# ROV_SensorBoard.net
KiCad netlist of a schematic drawn in Altium Designer
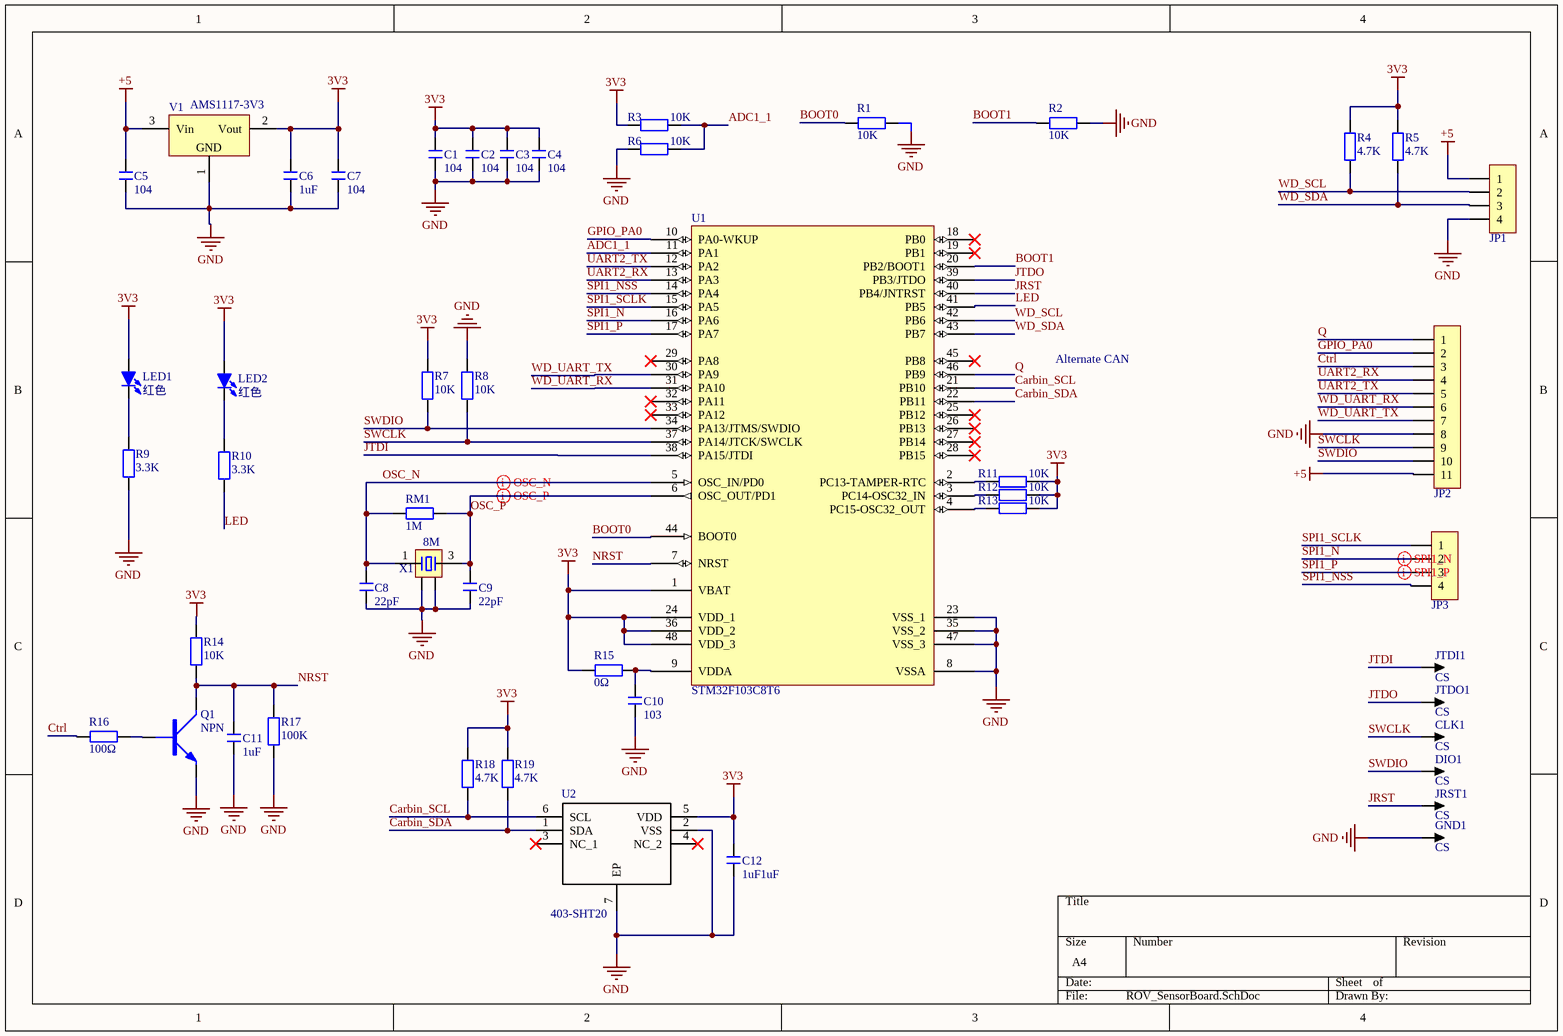
[diagram p0: ROV_SensorBoard.SchDoc]

(export (version "E")
  (design (tool "Eeschema 10.0.6"))
  (components
    (comp (ref "C1")
      (value "104")
      (footprint "C 0603_L")
      (description "无极性贴片电容")
      (fields (field (name "版权归属") "源创客"))
      (libsource (lib "3.1   - 电阻-电容-电感") (part "C"))
    )
    (comp (ref "C2")
      (value "104")
      (footprint "C 0603_L")
      (description "无极性贴片电容")
      (fields (field (name "版权归属") "源创客"))
      (libsource (lib "3.1   - 电阻-电容-电感") (part "C"))
    )
    (comp (ref "C3")
      (value "104")
      (footprint "C 0603_L")
      (description "无极性贴片电容")
      (fields (field (name "版权归属") "源创客"))
      (libsource (lib "3.1   - 电阻-电容-电感") (part "C"))
    )
    (comp (ref "C4")
      (value "104")
      (footprint "C 0603_L")
      (description "无极性贴片电容")
      (fields (field (name "版权归属") "源创客"))
      (libsource (lib "3.1   - 电阻-电容-电感") (part "C"))
    )
    (comp (ref "C5")
      (value "104")
      (footprint "C 0603_L")
      (description "无极性贴片电容")
      (fields (field (name "版权归属") "源创客"))
      (libsource (lib "3.1   - 电阻-电容-电感") (part "C"))
    )
    (comp (ref "C6")
      (value "1uF")
      (footprint "C 0603_L")
      (description "无极性贴片电容")
      (fields (field (name "版权归属") "源创客"))
      (libsource (lib "3.1   - 电阻-电容-电感") (part "C"))
    )
    (comp (ref "C7")
      (value "104")
      (footprint "C 0603_L")
      (description "无极性贴片电容")
      (fields (field (name "版权归属") "源创客"))
      (libsource (lib "3.1   - 电阻-电容-电感") (part "C"))
    )
    (comp (ref "C8")
      (value "22pF")
      (footprint "C 0603_L")
      (description "无极性贴片电容")
      (fields (field (name "版权归属") "源创客"))
      (libsource (lib "3.1   - 电阻-电容-电感") (part "C"))
    )
    (comp (ref "C9")
      (value "22pF")
      (footprint "C 0603_L")
      (description "无极性贴片电容")
      (fields (field (name "版权归属") "源创客"))
      (libsource (lib "3.1   - 电阻-电容-电感") (part "C"))
    )
    (comp (ref "C10")
      (value "103")
      (footprint "C 0603_L")
      (description "无极性贴片电容")
      (fields (field (name "版权归属") "源创客"))
      (libsource (lib "3.1   - 电阻-电容-电感") (part "C"))
    )
    (comp (ref "C11")
      (value "1uF")
      (footprint "C 0603_L")
      (description "无极性贴片电容")
      (fields (field (name "版权归属") "源创客"))
      (libsource (lib "3.1   - 电阻-电容-电感") (part "C"))
    )
    (comp (ref "C12")
      (value "1uF1uF")
      (footprint "C 0603_L")
      (description "无极性贴片电容")
      (fields (field (name "版权归属") "源创客"))
      (libsource (lib "3.1   - 电阻-电容-电感") (part "C"))
    )
    (comp (ref "CLK1")
      (value "CS")
      (footprint "R100")
      (description "探针焊盘")
      (fields (field (name "版权归属") "源创客"))
      (libsource (lib "15.1 - 未分类器件") (part "CS"))
    )
    (comp (ref "DIO1")
      (value "CS")
      (footprint "R100")
      (description "探针焊盘")
      (fields (field (name "版权归属") "源创客"))
      (libsource (lib "15.1 - 未分类器件") (part "CS"))
    )
    (comp (ref "GND1")
      (value "CS")
      (footprint "R100")
      (description "探针焊盘")
      (fields (field (name "版权归属") "源创客"))
      (libsource (lib "15.1 - 未分类器件") (part "CS"))
    )
    (comp (ref "JP1")
      (value "HDR-1X4")
      (footprint "MX 1.25-LS-4P")
      (description "4P接插件")
      (fields (field (name "版权归属") "源创客"))
      (libsource (lib "4.2   - 接插件-脚距1.25") (part "Header 4"))
    )
    (comp (ref "JP2")
      (value "HDR-1X11")
      (footprint "HDR2.54-LI-11P")
      (description "11P接插件")
      (fields (field (name "版权归属") "源创客"))
      (libsource (lib "4.5   - 接插件-脚距2.54") (part "Header 11"))
    )
    (comp (ref "JP3")
      (value "HDR-1X4")
      (footprint "HDR2.54-LI-4P")
      (description "4P接插件")
      (fields (field (name "版权归属") "源创客"))
      (libsource (lib "4.5   - 接插件-脚距2.54") (part "Header 4"))
    )
    (comp (ref "JRST1")
      (value "CS")
      (footprint "R100")
      (description "探针焊盘")
      (fields (field (name "版权归属") "源创客"))
      (libsource (lib "15.1 - 未分类器件") (part "CS"))
    )
    (comp (ref "JTDI1")
      (value "CS")
      (footprint "R100")
      (description "探针焊盘")
      (fields (field (name "版权归属") "源创客"))
      (libsource (lib "15.1 - 未分类器件") (part "CS"))
    )
    (comp (ref "JTDO1")
      (value "CS")
      (footprint "R100")
      (description "探针焊盘")
      (fields (field (name "版权归属") "源创客"))
      (libsource (lib "15.1 - 未分类器件") (part "CS"))
    )
    (comp (ref "LED1")
      (value "红色")
      (footprint "LED 0603W")
      (description "贴片LED")
      (fields (field (name "版权归属") "源创客"))
      (libsource (lib "9.1   - LED") (part "LED-SMD"))
    )
    (comp (ref "LED2")
      (value "红色")
      (footprint "LED 0603W")
      (description "贴片LED")
      (fields (field (name "版权归属") "源创客"))
      (libsource (lib "9.1   - LED") (part "LED-SMD"))
    )
    (comp (ref "Q1")
      (value "NPN")
      (footprint "SOT-23")
      (description "NPN三极管")
      (libsource (lib "三极管") (part "NPN"))
    )
    (comp (ref "R1")
      (value "10K")
      (footprint "R 0603_L")
      (description "贴片电阻")
      (fields (field (name "版权归属") "源创客"))
      (libsource (lib "3.1   - 电阻-电容-电感") (part "R"))
    )
    (comp (ref "R2")
      (value "10K")
      (footprint "R 0603_L")
      (description "贴片电阻")
      (fields (field (name "版权归属") "源创客"))
      (libsource (lib "3.1   - 电阻-电容-电感") (part "R"))
    )
    (comp (ref "R3")
      (value "10K")
      (footprint "R 0603_L")
      (description "贴片电阻")
      (fields (field (name "版权归属") "源创客"))
      (libsource (lib "3.1   - 电阻-电容-电感") (part "R"))
    )
    (comp (ref "R4")
      (value "4.7K")
      (footprint "R 0603_L")
      (description "贴片电阻")
      (fields (field (name "版权归属") "源创客"))
      (libsource (lib "3.1   - 电阻-电容-电感") (part "R"))
    )
    (comp (ref "R5")
      (value "4.7K")
      (footprint "R 0603_L")
      (description "贴片电阻")
      (fields (field (name "版权归属") "源创客"))
      (libsource (lib "3.1   - 电阻-电容-电感") (part "R"))
    )
    (comp (ref "R6")
      (value "10K")
      (footprint "R 0603_L")
      (description "贴片电阻")
      (fields (field (name "版权归属") "源创客"))
      (libsource (lib "3.1   - 电阻-电容-电感") (part "R"))
    )
    (comp (ref "R7")
      (value "10K")
      (footprint "R 0603_L")
      (description "贴片电阻")
      (fields (field (name "版权归属") "源创客"))
      (libsource (lib "3.1   - 电阻-电容-电感") (part "R"))
    )
    (comp (ref "R8")
      (value "10K")
      (footprint "R 0603_L")
      (description "贴片电阻")
      (fields (field (name "版权归属") "源创客"))
      (libsource (lib "3.1   - 电阻-电容-电感") (part "R"))
    )
    (comp (ref "R9")
      (value "3.3K")
      (footprint "R 0603_L")
      (description "贴片电阻")
      (fields (field (name "版权归属") "源创客"))
      (libsource (lib "3.1   - 电阻-电容-电感") (part "R"))
    )
    (comp (ref "R10")
      (value "3.3K")
      (footprint "R 0603_L")
      (description "贴片电阻")
      (fields (field (name "版权归属") "源创客"))
      (libsource (lib "3.1   - 电阻-电容-电感") (part "R"))
    )
    (comp (ref "R11")
      (value "10K")
      (footprint "R 0603_L")
      (description "贴片电阻")
      (fields (field (name "版权归属") "源创客"))
      (libsource (lib "3.1   - 电阻-电容-电感") (part "R"))
    )
    (comp (ref "R12")
      (value "10K")
      (footprint "R 0603_L")
      (description "贴片电阻")
      (fields (field (name "版权归属") "源创客"))
      (libsource (lib "3.1   - 电阻-电容-电感") (part "R"))
    )
    (comp (ref "R13")
      (value "10K")
      (footprint "R 0603_L")
      (description "贴片电阻")
      (fields (field (name "版权归属") "源创客"))
      (libsource (lib "3.1   - 电阻-电容-电感") (part "R"))
    )
    (comp (ref "R14")
      (value "10K")
      (footprint "R 0603_L")
      (description "贴片电阻")
      (fields (field (name "版权归属") "源创客"))
      (libsource (lib "3.1   - 电阻-电容-电感") (part "R"))
    )
    (comp (ref "R15")
      (value "0Ω")
      (footprint "R 0603_L")
      (description "贴片电阻")
      (fields (field (name "版权归属") "源创客"))
      (libsource (lib "3.1   - 电阻-电容-电感") (part "R"))
    )
    (comp (ref "R16")
      (value "100Ω")
      (footprint "R 0603_L")
      (description "贴片电阻")
      (fields (field (name "版权归属") "源创客"))
      (libsource (lib "3.1   - 电阻-电容-电感") (part "R"))
    )
    (comp (ref "R17")
      (value "100K")
      (footprint "R 0603_L")
      (description "贴片电阻")
      (fields (field (name "版权归属") "源创客"))
      (libsource (lib "3.1   - 电阻-电容-电感") (part "R"))
    )
    (comp (ref "R18")
      (value "4.7K")
      (footprint "R 0603_L")
      (description "贴片电阻")
      (fields (field (name "版权归属") "源创客"))
      (libsource (lib "3.1   - 电阻-电容-电感") (part "R"))
    )
    (comp (ref "R19")
      (value "4.7K")
      (footprint "R 0603_L")
      (description "贴片电阻")
      (fields (field (name "版权归属") "源创客"))
      (libsource (lib "3.1   - 电阻-电容-电感") (part "R"))
    )
    (comp (ref "RM1")
      (value "1M")
      (footprint "R 0603_L")
      (description "贴片电阻")
      (fields (field (name "版权归属") "源创客"))
      (libsource (lib "3.1   - 电阻-电容-电感") (part "R"))
    )
    (comp (ref "U1")
      (value "STM32F103C8T6")
      (footprint "LQFP48 7X7")
      (libsource (lib "STM32系列") (part "STM32F103C8T6"))
    )
    (comp (ref "U2")
      (value "SHT20")
      (footprint "SON100P300X300X110-7N")
      (description "温湿度传感器")
      (fields (field (name "RS PART NUMBER") "1237351P") (field (name "MOUSER PART NUMBER") "403-SHT20"))
      (libsource (lib "MySchLib") (part "SHT20"))
    )
    (comp (ref "V1")
      (value "AMS1117-3V3")
      (footprint "SOT89_N")
      (description "三端稳压芯片")
      (fields (field (name "版权归属") "源创客"))
      (libsource (lib "1.3   - 电源类芯片") (part "AMS1117"))
    )
    (comp (ref "X1")
      (value "8M")
      (footprint "OSC 5032-4P")
      (description "4脚无源晶振")
      (fields (field (name "版权归属") "源创客"))
      (libsource (lib "10.1 - 保险丝-晶振") (part "XTAL-4P"))
    )
  )
  (nets
    (net (code "1") (name "+5") (class "Default")
      (node (ref "C5") (pin "2") (pinfunction "2_2") (pintype "passive"))
      (node (ref "JP1") (pin "1") (pinfunction "1_1") (pintype "passive"))
      (node (ref "JP2") (pin "11") (pinfunction "11_11") (pintype "passive"))
      (node (ref "V1") (pin "3") (pinfunction "Vin_3") (pintype "passive"))
    )
    (net (code "2") (name "/ADC1_1") (class "Default")
      (node (ref "R3") (pin "1") (pinfunction "1_1") (pintype "passive"))
      (node (ref "R6") (pin "1") (pinfunction "1_1") (pintype "passive"))
      (node (ref "U1") (pin "11") (pinfunction "PA1_11") (pintype "bidirectional"))
    )
    (net (code "3") (name "/BOOT0") (class "Default")
      (node (ref "R1") (pin "2") (pinfunction "2_2") (pintype "passive"))
      (node (ref "U1") (pin "44") (pinfunction "BOOT0_44") (pintype "input"))
    )
    (net (code "4") (name "/BOOT1") (class "Default")
      (node (ref "R2") (pin "2") (pinfunction "2_2") (pintype "passive"))
      (node (ref "U1") (pin "20") (pinfunction "PB2/BOOT1_20") (pintype "bidirectional"))
    )
    (net (code "5") (name "/Carbin_SCL") (class "Default")
      (node (ref "R18") (pin "1") (pinfunction "1_1") (pintype "passive"))
      (node (ref "U1") (pin "21") (pinfunction "PB10_21") (pintype "bidirectional"))
      (node (ref "U2") (pin "6") (pinfunction "SCL_6") (pintype "passive"))
    )
    (net (code "6") (name "/Carbin_SDA") (class "Default")
      (node (ref "R19") (pin "1") (pinfunction "1_1") (pintype "passive"))
      (node (ref "U1") (pin "22") (pinfunction "PB11_22") (pintype "bidirectional"))
      (node (ref "U2") (pin "1") (pinfunction "SDA_1") (pintype "passive"))
    )
    (net (code "7") (name "/Ctrl") (class "Default")
      (node (ref "JP2") (pin "3") (pinfunction "3_3") (pintype "passive"))
      (node (ref "R16") (pin "2") (pinfunction "2_2") (pintype "passive"))
    )
    (net (code "8") (name "/GPIO_PA0") (class "Default")
      (node (ref "JP2") (pin "2") (pinfunction "2_2") (pintype "passive"))
      (node (ref "U1") (pin "10") (pinfunction "PA0-WKUP_10") (pintype "bidirectional"))
    )
    (net (code "9") (name "/JRST") (class "Default")
      (node (ref "JRST1") (pin "1") (pinfunction "1_1") (pintype "passive"))
      (node (ref "U1") (pin "40") (pinfunction "PB4/JNTRST_40") (pintype "bidirectional"))
    )
    (net (code "10") (name "/JTDI") (class "Default")
      (node (ref "JTDI1") (pin "1") (pinfunction "1_1") (pintype "passive"))
      (node (ref "U1") (pin "38") (pinfunction "PA15/JTDI_38") (pintype "bidirectional"))
    )
    (net (code "11") (name "/JTDO") (class "Default")
      (node (ref "JTDO1") (pin "1") (pinfunction "1_1") (pintype "passive"))
      (node (ref "U1") (pin "39") (pinfunction "PB3/JTDO_39") (pintype "bidirectional"))
    )
    (net (code "12") (name "/LED") (class "Default")
      (node (ref "R10") (pin "1") (pinfunction "1_1") (pintype "passive"))
      (node (ref "U1") (pin "41") (pinfunction "PB5_41") (pintype "bidirectional"))
    )
    (net (code "13") (name "/NRST") (class "Default")
      (node (ref "C11") (pin "2") (pinfunction "2_2") (pintype "passive"))
      (node (ref "Q1") (pin "C") (pinfunction "C_C") (pintype "passive"))
      (node (ref "R14") (pin "2") (pinfunction "2_2") (pintype "passive"))
      (node (ref "R17") (pin "1") (pinfunction "1_1") (pintype "passive"))
      (node (ref "U1") (pin "7") (pinfunction "NRST_7") (pintype "bidirectional"))
    )
    (net (code "14") (name "/OSC_N") (class "Default")
      (node (ref "C8") (pin "2") (pinfunction "2_2") (pintype "passive"))
      (node (ref "RM1") (pin "2") (pinfunction "2_2") (pintype "passive"))
      (node (ref "U1") (pin "5") (pinfunction "OSC_IN/PD0_5") (pintype "input"))
      (node (ref "X1") (pin "1") (pinfunction "1_1") (pintype "passive"))
    )
    (net (code "15") (name "/OSC_P") (class "Default")
      (node (ref "C9") (pin "2") (pinfunction "2_2") (pintype "passive"))
      (node (ref "RM1") (pin "1") (pinfunction "1_1") (pintype "passive"))
      (node (ref "U1") (pin "6") (pinfunction "OSC_OUT/PD1_6") (pintype "output"))
      (node (ref "X1") (pin "3") (pinfunction "3_3") (pintype "passive"))
    )
    (net (code "16") (name "/Q") (class "Default")
      (node (ref "JP2") (pin "1") (pinfunction "1_1") (pintype "passive"))
      (node (ref "U1") (pin "46") (pinfunction "PB9_46") (pintype "bidirectional"))
    )
    (net (code "17") (name "/SPI1_N") (class "Default")
      (node (ref "JP3") (pin "2") (pinfunction "2_2") (pintype "passive"))
      (node (ref "U1") (pin "16") (pinfunction "PA6_16") (pintype "bidirectional"))
    )
    (net (code "18") (name "/SPI1_NSS") (class "Default")
      (node (ref "JP3") (pin "4") (pinfunction "4_4") (pintype "passive"))
      (node (ref "U1") (pin "14") (pinfunction "PA4_14") (pintype "bidirectional"))
    )
    (net (code "19") (name "/SPI1_P") (class "Default")
      (node (ref "JP3") (pin "3") (pinfunction "3_3") (pintype "passive"))
      (node (ref "U1") (pin "17") (pinfunction "PA7_17") (pintype "bidirectional"))
    )
    (net (code "20") (name "/SPI1_SCLK") (class "Default")
      (node (ref "JP3") (pin "1") (pinfunction "1_1") (pintype "passive"))
      (node (ref "U1") (pin "15") (pinfunction "PA5_15") (pintype "bidirectional"))
    )
    (net (code "21") (name "/SWCLK") (class "Default")
      (node (ref "CLK1") (pin "1") (pinfunction "1_1") (pintype "passive"))
      (node (ref "JP2") (pin "9") (pinfunction "9_9") (pintype "passive"))
      (node (ref "R8") (pin "2") (pinfunction "2_2") (pintype "passive"))
      (node (ref "U1") (pin "37") (pinfunction "PA14/JTCK/SWCLK_37") (pintype "bidirectional"))
    )
    (net (code "22") (name "/SWDIO") (class "Default")
      (node (ref "DIO1") (pin "1") (pinfunction "1_1") (pintype "passive"))
      (node (ref "JP2") (pin "10") (pinfunction "10_10") (pintype "passive"))
      (node (ref "R7") (pin "2") (pinfunction "2_2") (pintype "passive"))
      (node (ref "U1") (pin "34") (pinfunction "PA13/JTMS/SWDIO_34") (pintype "bidirectional"))
    )
    (net (code "23") (name "/UART2_RX") (class "Default")
      (node (ref "JP2") (pin "4") (pinfunction "4_4") (pintype "passive"))
      (node (ref "U1") (pin "13") (pinfunction "PA3_13") (pintype "bidirectional"))
    )
    (net (code "24") (name "/UART2_TX") (class "Default")
      (node (ref "JP2") (pin "5") (pinfunction "5_5") (pintype "passive"))
      (node (ref "U1") (pin "12") (pinfunction "PA2_12") (pintype "bidirectional"))
    )
    (net (code "25") (name "/WD_SCL") (class "Default")
      (node (ref "JP1") (pin "2") (pinfunction "2_2") (pintype "passive"))
      (node (ref "R4") (pin "1") (pinfunction "1_1") (pintype "passive"))
      (node (ref "U1") (pin "42") (pinfunction "PB6_42") (pintype "bidirectional"))
    )
    (net (code "26") (name "/WD_SDA") (class "Default")
      (node (ref "JP1") (pin "3") (pinfunction "3_3") (pintype "passive"))
      (node (ref "R5") (pin "1") (pinfunction "1_1") (pintype "passive"))
      (node (ref "U1") (pin "43") (pinfunction "PB7_43") (pintype "bidirectional"))
    )
    (net (code "27") (name "/WD_UART_RX") (class "Default")
      (node (ref "JP2") (pin "6") (pinfunction "6_6") (pintype "passive"))
      (node (ref "U1") (pin "31") (pinfunction "PA10_31") (pintype "bidirectional"))
    )
    (net (code "28") (name "/WD_UART_TX") (class "Default")
      (node (ref "JP2") (pin "7") (pinfunction "7_7") (pintype "passive"))
      (node (ref "U1") (pin "30") (pinfunction "PA9_30") (pintype "bidirectional"))
    )
    (net (code "29") (name "3V3") (class "Default")
      (node (ref "C1") (pin "2") (pinfunction "2_2") (pintype "passive"))
      (node (ref "C12") (pin "2") (pinfunction "2_2") (pintype "passive"))
      (node (ref "C2") (pin "2") (pinfunction "2_2") (pintype "passive"))
      (node (ref "C3") (pin "2") (pinfunction "2_2") (pintype "passive"))
      (node (ref "C4") (pin "2") (pinfunction "2_2") (pintype "passive"))
      (node (ref "C6") (pin "2") (pinfunction "2_2") (pintype "passive"))
      (node (ref "C7") (pin "2") (pinfunction "2_2") (pintype "passive"))
      (node (ref "LED1") (pin "1") (pinfunction "A_1") (pintype "passive"))
      (node (ref "LED2") (pin "1") (pinfunction "A_1") (pintype "passive"))
      (node (ref "R11") (pin "1") (pinfunction "1_1") (pintype "passive"))
      (node (ref "R12") (pin "1") (pinfunction "1_1") (pintype "passive"))
      (node (ref "R13") (pin "1") (pinfunction "1_1") (pintype "passive"))
      (node (ref "R14") (pin "1") (pinfunction "1_1") (pintype "passive"))
      (node (ref "R15") (pin "2") (pinfunction "2_2") (pintype "passive"))
      (node (ref "R18") (pin "2") (pinfunction "2_2") (pintype "passive"))
      (node (ref "R19") (pin "2") (pinfunction "2_2") (pintype "passive"))
      (node (ref "R3") (pin "2") (pinfunction "2_2") (pintype "passive"))
      (node (ref "R4") (pin "2") (pinfunction "2_2") (pintype "passive"))
      (node (ref "R5") (pin "2") (pinfunction "2_2") (pintype "passive"))
      (node (ref "R7") (pin "1") (pinfunction "1_1") (pintype "passive"))
      (node (ref "U1") (pin "1") (pinfunction "VBAT_1") (pintype "power_in"))
      (node (ref "U1") (pin "24") (pinfunction "VDD_1_24") (pintype "power_in"))
      (node (ref "U1") (pin "36") (pinfunction "VDD_2_36") (pintype "power_in"))
      (node (ref "U1") (pin "48") (pinfunction "VDD_3_48") (pintype "power_in"))
      (node (ref "U2") (pin "5") (pinfunction "VDD_5") (pintype "passive"))
      (node (ref "V1") (pin "2") (pinfunction "Vout_2") (pintype "passive"))
    )
    (net (code "30") (name "GND") (class "Default")
      (node (ref "C1") (pin "1") (pinfunction "1_1") (pintype "passive"))
      (node (ref "C10") (pin "1") (pinfunction "1_1") (pintype "passive"))
      (node (ref "C11") (pin "1") (pinfunction "1_1") (pintype "passive"))
      (node (ref "C12") (pin "1") (pinfunction "1_1") (pintype "passive"))
      (node (ref "C2") (pin "1") (pinfunction "1_1") (pintype "passive"))
      (node (ref "C3") (pin "1") (pinfunction "1_1") (pintype "passive"))
      (node (ref "C4") (pin "1") (pinfunction "1_1") (pintype "passive"))
      (node (ref "C5") (pin "1") (pinfunction "1_1") (pintype "passive"))
      (node (ref "C6") (pin "1") (pinfunction "1_1") (pintype "passive"))
      (node (ref "C7") (pin "1") (pinfunction "1_1") (pintype "passive"))
      (node (ref "C8") (pin "1") (pinfunction "1_1") (pintype "passive"))
      (node (ref "C9") (pin "1") (pinfunction "1_1") (pintype "passive"))
      (node (ref "GND1") (pin "1") (pinfunction "1_1") (pintype "passive"))
      (node (ref "JP1") (pin "4") (pinfunction "4_4") (pintype "passive"))
      (node (ref "JP2") (pin "8") (pinfunction "8_8") (pintype "passive"))
      (node (ref "Q1") (pin "E") (pinfunction "E_E") (pintype "passive"))
      (node (ref "R1") (pin "1") (pinfunction "1_1") (pintype "passive"))
      (node (ref "R17") (pin "2") (pinfunction "2_2") (pintype "passive"))
      (node (ref "R2") (pin "1") (pinfunction "1_1") (pintype "passive"))
      (node (ref "R6") (pin "2") (pinfunction "2_2") (pintype "passive"))
      (node (ref "R8") (pin "1") (pinfunction "1_1") (pintype "passive"))
      (node (ref "R9") (pin "1") (pinfunction "1_1") (pintype "passive"))
      (node (ref "U1") (pin "23") (pinfunction "VSS_1_23") (pintype "power_in"))
      (node (ref "U1") (pin "35") (pinfunction "VSS_2_35") (pintype "power_in"))
      (node (ref "U1") (pin "47") (pinfunction "VSS_3_47") (pintype "power_in"))
      (node (ref "U1") (pin "8") (pinfunction "VSSA_8") (pintype "power_in"))
      (node (ref "U2") (pin "2") (pinfunction "VSS_2") (pintype "passive"))
      (node (ref "U2") (pin "7") (pinfunction "EP_7") (pintype "passive"))
      (node (ref "V1") (pin "1") (pinfunction "GND_1") (pintype "passive"))
      (node (ref "X1") (pin "2") (pinfunction "2_2") (pintype "passive"))
      (node (ref "X1") (pin "4") (pinfunction "4_4") (pintype "passive"))
    )
    (net (code "31") (name "Net-(LED1-K)") (class "Default")
      (node (ref "LED1") (pin "2") (pinfunction "K_2") (pintype "passive"))
      (node (ref "R9") (pin "2") (pinfunction "2_2") (pintype "passive"))
    )
    (net (code "32") (name "Net-(LED2-K)") (class "Default")
      (node (ref "LED2") (pin "2") (pinfunction "K_2") (pintype "passive"))
      (node (ref "R10") (pin "2") (pinfunction "2_2") (pintype "passive"))
    )
    (net (code "33") (name "Net-(Q1-PadB)") (class "Default")
      (node (ref "Q1") (pin "B") (pinfunction "B_B") (pintype "passive"))
      (node (ref "R16") (pin "1") (pinfunction "1_1") (pintype "passive"))
    )
    (net (code "34") (name "Net-(U1-PC13-TAMPER-RTC)") (class "Default")
      (node (ref "R11") (pin "2") (pinfunction "2_2") (pintype "passive"))
      (node (ref "U1") (pin "2") (pinfunction "PC13-TAMPER-RTC_2") (pintype "bidirectional"))
    )
    (net (code "35") (name "Net-(U1-PC14-OSC32_IN)") (class "Default")
      (node (ref "R12") (pin "2") (pinfunction "2_2") (pintype "passive"))
      (node (ref "U1") (pin "3") (pinfunction "PC14-OSC32_IN_3") (pintype "bidirectional"))
    )
    (net (code "36") (name "Net-(U1-PC15-OSC32_OUT)") (class "Default")
      (node (ref "R13") (pin "2") (pinfunction "2_2") (pintype "passive"))
      (node (ref "U1") (pin "4") (pinfunction "PC15-OSC32_OUT_4") (pintype "bidirectional"))
    )
    (net (code "37") (name "Net-(U1-VDDA)") (class "Default")
      (node (ref "C10") (pin "2") (pinfunction "2_2") (pintype "passive"))
      (node (ref "R15") (pin "1") (pinfunction "1_1") (pintype "passive"))
      (node (ref "U1") (pin "9") (pinfunction "VDDA_9") (pintype "power_in"))
    )
    (net (code "38") (name "unconnected-(U1-PA8-Pad29)") (class "Default")
      (node (ref "U1") (pin "29") (pinfunction "PA8_29") (pintype "bidirectional+no_connect"))
    )
    (net (code "39") (name "unconnected-(U1-PA11-Pad32)") (class "Default")
      (node (ref "U1") (pin "32") (pinfunction "PA11_32") (pintype "bidirectional+no_connect"))
    )
    (net (code "40") (name "unconnected-(U1-PA12-Pad33)") (class "Default")
      (node (ref "U1") (pin "33") (pinfunction "PA12_33") (pintype "bidirectional+no_connect"))
    )
    (net (code "41") (name "unconnected-(U1-PB0-Pad18)") (class "Default")
      (node (ref "U1") (pin "18") (pinfunction "PB0_18") (pintype "bidirectional+no_connect"))
    )
    (net (code "42") (name "unconnected-(U1-PB1-Pad19)") (class "Default")
      (node (ref "U1") (pin "19") (pinfunction "PB1_19") (pintype "bidirectional+no_connect"))
    )
    (net (code "43") (name "unconnected-(U1-PB8-Pad45)") (class "Default")
      (node (ref "U1") (pin "45") (pinfunction "PB8_45") (pintype "bidirectional+no_connect"))
    )
    (net (code "44") (name "unconnected-(U1-PB12-Pad25)") (class "Default")
      (node (ref "U1") (pin "25") (pinfunction "PB12_25") (pintype "bidirectional+no_connect"))
    )
    (net (code "45") (name "unconnected-(U1-PB13-Pad26)") (class "Default")
      (node (ref "U1") (pin "26") (pinfunction "PB13_26") (pintype "bidirectional+no_connect"))
    )
    (net (code "46") (name "unconnected-(U1-PB14-Pad27)") (class "Default")
      (node (ref "U1") (pin "27") (pinfunction "PB14_27") (pintype "bidirectional+no_connect"))
    )
    (net (code "47") (name "unconnected-(U1-PB15-Pad28)") (class "Default")
      (node (ref "U1") (pin "28") (pinfunction "PB15_28") (pintype "bidirectional+no_connect"))
    )
    (net (code "48") (name "unconnected-(U2-NC_1-Pad3)") (class "Default")
      (node (ref "U2") (pin "3") (pinfunction "NC_1_3") (pintype "passive+no_connect"))
    )
    (net (code "49") (name "unconnected-(U2-NC_2-Pad4)") (class "Default")
      (node (ref "U2") (pin "4") (pinfunction "NC_2_4") (pintype "passive+no_connect"))
    )
  )
)
